# Tenk.net
KiCad netlist of a schematic drawn in Altium Designer
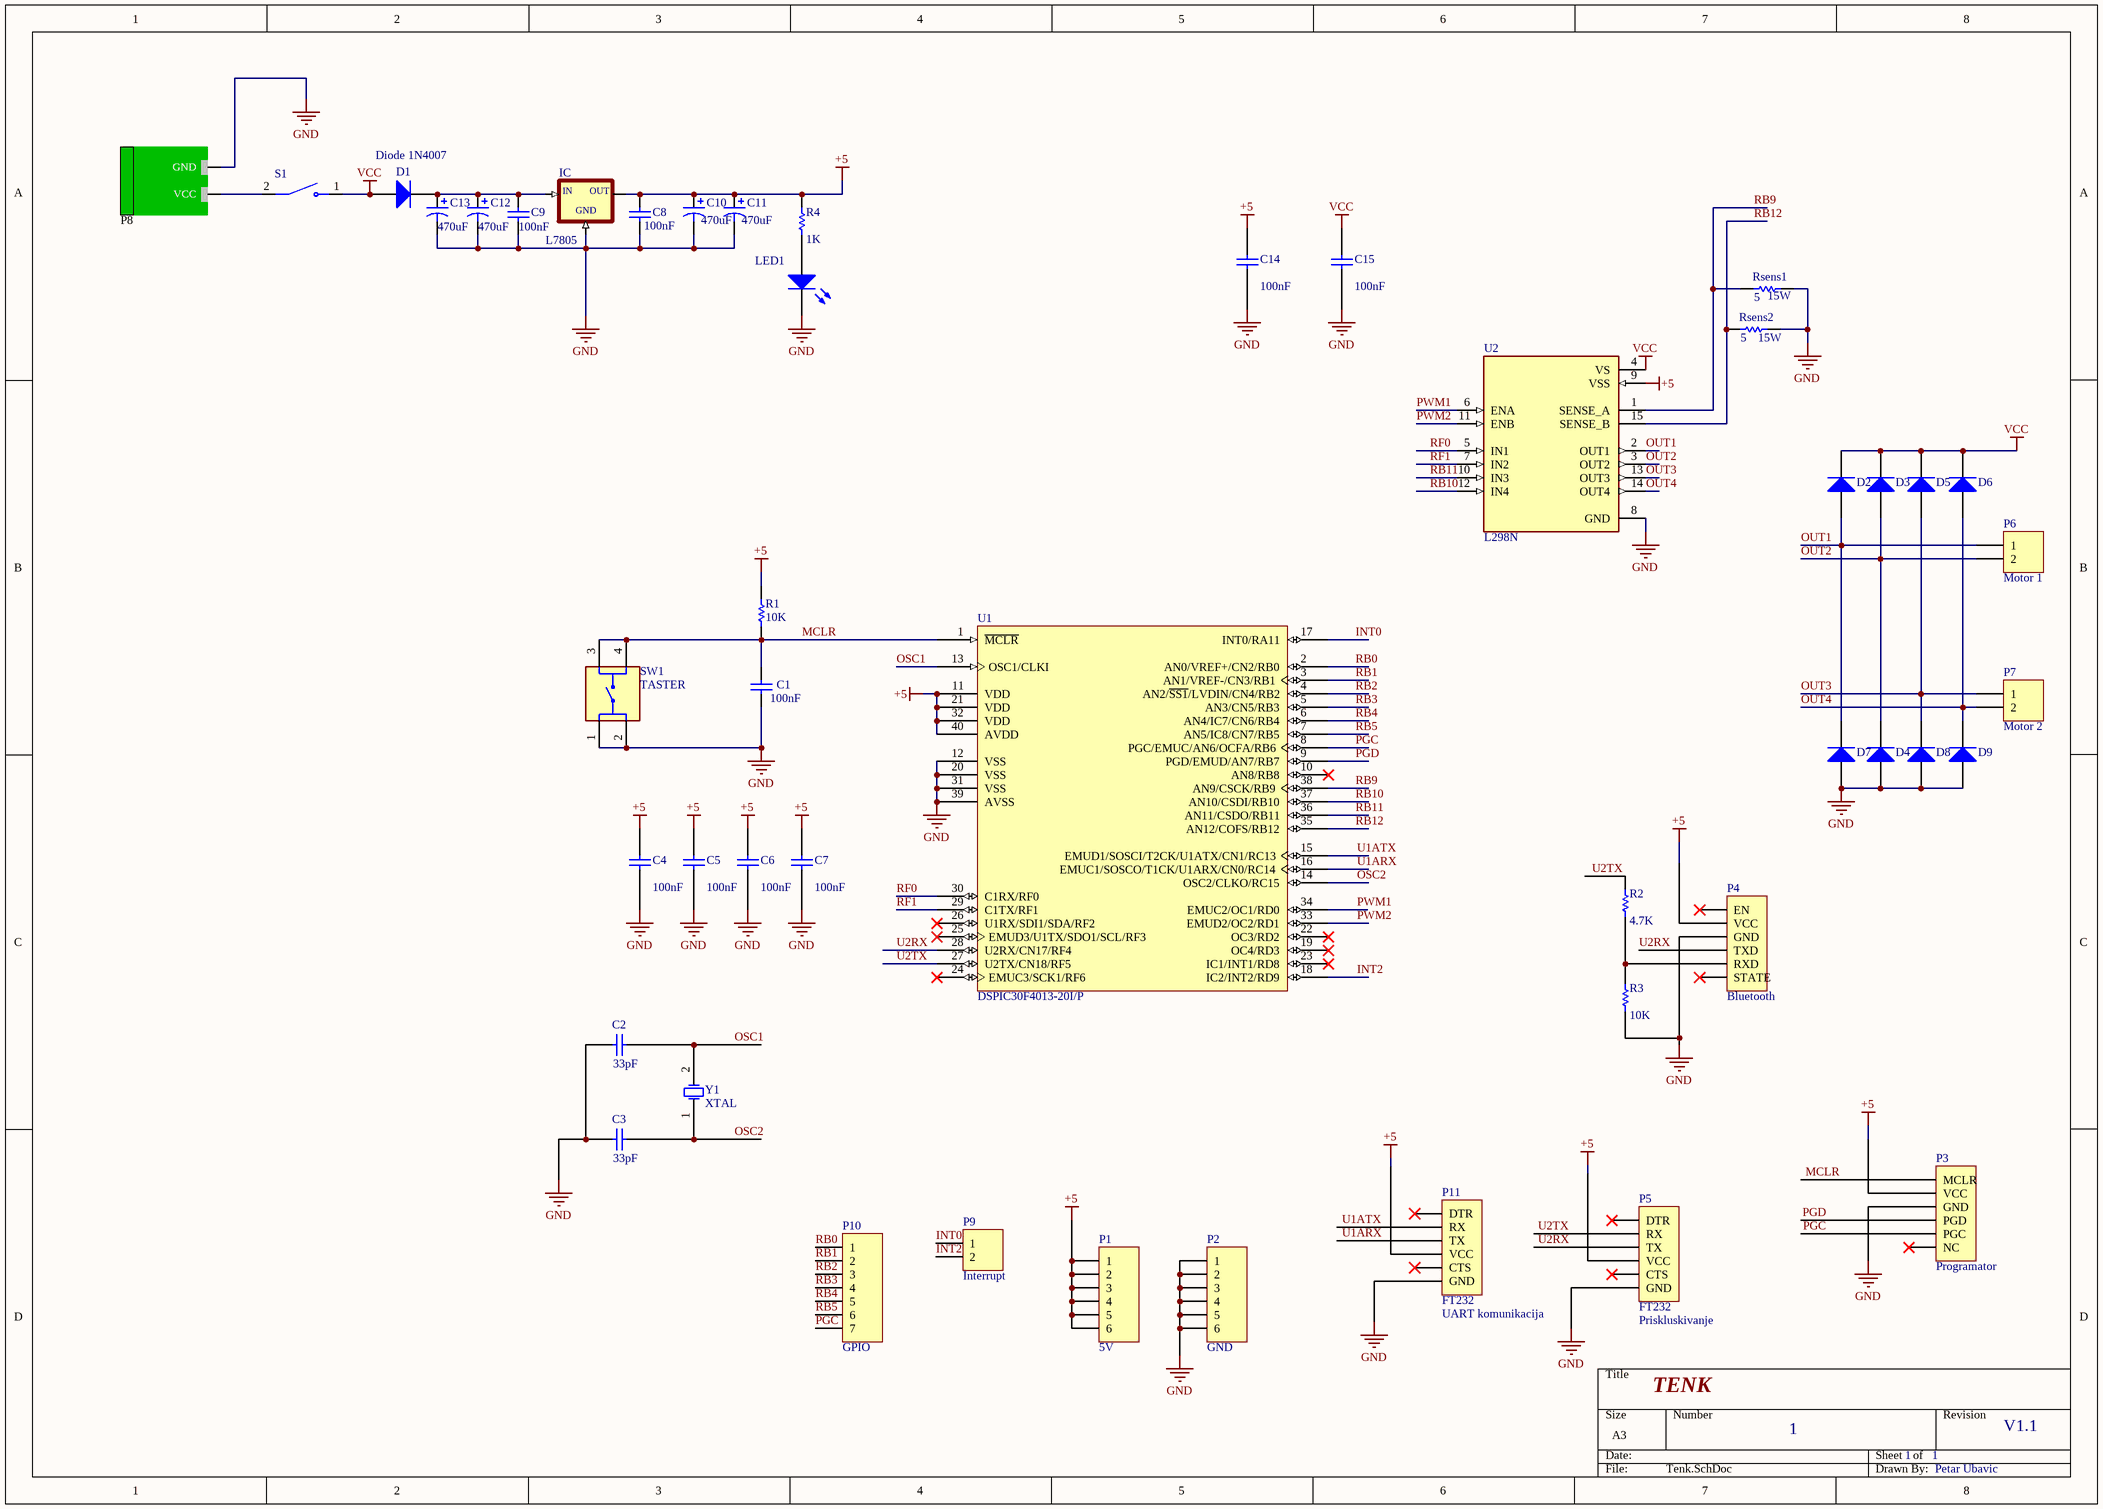
[diagram p0: Tenk.SchDoc]

(export (version "E")
  (design (tool "Eeschema 10.0.6"))
  (components
    (comp (ref "C1")
      (value "100nF")
      (footprint "CAP100")
      (description "Capacitor")
      (fields (field (name "Comment") "Cap") (field (name "PUBLISHER") "Altium Limited"))
      (libsource (lib "Miscellaneous Devices") (part "Cap"))
    )
    (comp (ref "C2")
      (value "33pF")
      (footprint "CAP100")
      (description "Capacitor")
      (fields (field (name "Comment") "Cap") (field (name "PUBLISHER") "Altium Limited"))
      (libsource (lib "Miscellaneous Devices") (part "Cap"))
    )
    (comp (ref "C3")
      (value "33pF")
      (footprint "CAP100")
      (description "Capacitor")
      (fields (field (name "Comment") "Cap") (field (name "PUBLISHER") "Altium Limited"))
      (libsource (lib "Miscellaneous Devices") (part "Cap"))
    )
    (comp (ref "C4")
      (value "100nF")
      (footprint "CAP100")
      (description "Capacitor")
      (fields (field (name "Comment") "Cap") (field (name "PUBLISHER") "Altium Limited"))
      (libsource (lib "Miscellaneous Devices") (part "Cap"))
    )
    (comp (ref "C5")
      (value "100nF")
      (footprint "CAP100")
      (description "Capacitor")
      (fields (field (name "Comment") "Cap") (field (name "PUBLISHER") "Altium Limited"))
      (libsource (lib "Miscellaneous Devices") (part "Cap"))
    )
    (comp (ref "C6")
      (value "100nF")
      (footprint "CAP100")
      (description "Capacitor")
      (fields (field (name "Comment") "Cap") (field (name "PUBLISHER") "Altium Limited"))
      (libsource (lib "Miscellaneous Devices") (part "Cap"))
    )
    (comp (ref "C7")
      (value "100nF")
      (footprint "CAP100")
      (description "Capacitor")
      (fields (field (name "Comment") "Cap") (field (name "PUBLISHER") "Altium Limited"))
      (libsource (lib "Miscellaneous Devices") (part "Cap"))
    )
    (comp (ref "C8")
      (value "100nF")
      (footprint "CAP100")
      (description "Capacitor")
      (fields (field (name "Comment") "Cap") (field (name "PUBLISHER") "Altium Limited"))
      (libsource (lib "Miscellaneous Devices") (part "Cap"))
    )
    (comp (ref "C9")
      (value "100nF")
      (footprint "CAP100")
      (description "Capacitor")
      (fields (field (name "Comment") "Cap") (field (name "PUBLISHER") "Altium Limited"))
      (libsource (lib "Miscellaneous Devices") (part "Cap"))
    )
    (comp (ref "C10")
      (value "470uF")
      (footprint "RAD4")
      (description "Polarized Capacitor (Radial)")
      (fields (field (name "Comment") "Cap Pol1") (field (name "PUBLISHER") "Altium Limited"))
      (libsource (lib "Miscellaneous Devices") (part "Cap Pol1"))
    )
    (comp (ref "C11")
      (value "470uF")
      (footprint "RAD4")
      (description "Polarized Capacitor (Radial)")
      (fields (field (name "Comment") "Cap Pol1") (field (name "PUBLISHER") "Altium Limited"))
      (libsource (lib "Miscellaneous Devices") (part "Cap Pol1"))
    )
    (comp (ref "C12")
      (value "470uF")
      (footprint "RAD4")
      (description "Polarized Capacitor (Radial)")
      (fields (field (name "Comment") "Cap Pol1") (field (name "PUBLISHER") "Altium Limited"))
      (libsource (lib "Miscellaneous Devices") (part "Cap Pol1"))
    )
    (comp (ref "C13")
      (value "470uF")
      (footprint "RAD4")
      (description "Polarized Capacitor (Radial)")
      (fields (field (name "Comment") "Cap Pol1") (field (name "PUBLISHER") "Altium Limited"))
      (libsource (lib "Miscellaneous Devices") (part "Cap Pol1"))
    )
    (comp (ref "C14")
      (value "100nF")
      (footprint "CAP100")
      (description "Capacitor")
      (fields (field (name "Comment") "Cap") (field (name "PUBLISHER") "Altium Limited"))
      (libsource (lib "Miscellaneous Devices") (part "Cap"))
    )
    (comp (ref "C15")
      (value "100nF")
      (footprint "CAP100")
      (description "Capacitor")
      (fields (field (name "Comment") "Cap") (field (name "PUBLISHER") "Altium Limited"))
      (libsource (lib "Miscellaneous Devices") (part "Cap"))
    )
    (comp (ref "D1")
      (value "Diode 1N4007")
      (footprint "DIODE400")
      (description "1 Amp General Purpose Rectifier")
      (fields (field (name "PUBLISHER") "Altium Limited"))
      (libsource (lib "Miscellaneous Devices") (part "Diode 1N4007"))
    )
    (comp (ref "D2")
      (value "Diode 1N5402")
      (footprint "DIODE400")
      (description "3 Amp General Purpose Rectifier")
      (fields (field (name "PUBLISHER") "Altium Limited"))
      (libsource (lib "Miscellaneous Devices") (part "Diode 1N5402"))
    )
    (comp (ref "D3")
      (value "Diode 1N5402")
      (footprint "DIODE400")
      (description "3 Amp General Purpose Rectifier")
      (fields (field (name "PUBLISHER") "Altium Limited"))
      (libsource (lib "Miscellaneous Devices") (part "Diode 1N5402"))
    )
    (comp (ref "D4")
      (value "Diode 1N5402")
      (footprint "DIODE400")
      (description "3 Amp General Purpose Rectifier")
      (fields (field (name "PUBLISHER") "Altium Limited"))
      (libsource (lib "Miscellaneous Devices") (part "Diode 1N5402"))
    )
    (comp (ref "D5")
      (value "Diode 1N5402")
      (footprint "DIODE400")
      (description "3 Amp General Purpose Rectifier")
      (fields (field (name "PUBLISHER") "Altium Limited"))
      (libsource (lib "Miscellaneous Devices") (part "Diode 1N5402"))
    )
    (comp (ref "D6")
      (value "Diode 1N5402")
      (footprint "DIODE400")
      (description "3 Amp General Purpose Rectifier")
      (fields (field (name "PUBLISHER") "Altium Limited"))
      (libsource (lib "Miscellaneous Devices") (part "Diode 1N5402"))
    )
    (comp (ref "D7")
      (value "Diode 1N5402")
      (footprint "DIODE400")
      (description "3 Amp General Purpose Rectifier")
      (fields (field (name "PUBLISHER") "Altium Limited"))
      (libsource (lib "Miscellaneous Devices") (part "Diode 1N5402"))
    )
    (comp (ref "D8")
      (value "Diode 1N5402")
      (footprint "DIODE400")
      (description "3 Amp General Purpose Rectifier")
      (fields (field (name "PUBLISHER") "Altium Limited"))
      (libsource (lib "Miscellaneous Devices") (part "Diode 1N5402"))
    )
    (comp (ref "D9")
      (value "Diode 1N5402")
      (footprint "DIODE400")
      (description "3 Amp General Purpose Rectifier")
      (fields (field (name "PUBLISHER") "Altium Limited"))
      (libsource (lib "Miscellaneous Devices") (part "Diode 1N5402"))
    )
    (comp (ref "IC")
      (value "L7805")
      (footprint "78XXS")
      (description "Linear Voltage Regulator IC 1 Output 1.5A D2PAK")
      (fields (field (name "MF") "STMicroelectronics"))
      (libsource (lib "L7805") (part "L7805"))
    )
    (comp (ref "LED1")
      (value "GREEN")
      (footprint "LED_2")
      (description "Typical RED GaAs LED")
      (fields (field (name "PUBLISHER") "Altium Limited"))
      (libsource (lib "Miscellaneous Devices") (part "LED1"))
    )
    (comp (ref "P1")
      (value "5V")
      (footprint "HEADER_6")
      (description "Header, 6-Pin")
      (fields (field (name "PUBLISHER") "Altium Limited"))
      (libsource (lib "Miscellaneous Connectors") (part "Header 6"))
    )
    (comp (ref "P2")
      (value "GND")
      (footprint "HEADER_6")
      (description "Header, 6-Pin")
      (fields (field (name "PUBLISHER") "Altium Limited"))
      (libsource (lib "Miscellaneous Connectors") (part "Header 6"))
    )
    (comp (ref "P3")
      (value "Programator")
      (footprint "HEADER_6")
      (description "Header, 6-Pin")
      (fields (field (name "PUBLISHER") "Altium Limited"))
      (libsource (lib "Miscellaneous Connectors") (part "Header 6"))
    )
    (comp (ref "P4")
      (value "Bluetooth")
      (footprint "HEADER_6")
      (description "Header, 6-Pin")
      (fields (field (name "PUBLISHER") "Altium Limited"))
      (libsource (lib "Miscellaneous Connectors") (part "Header 6"))
    )
    (comp (ref "P5")
      (value "FT232")
      (footprint "HEADER_6")
      (description "Header, 6-Pin")
      (fields (field (name "PUBLISHER") "Altium Limited"))
      (libsource (lib "Miscellaneous Connectors") (part "Header 6"))
    )
    (comp (ref "P6")
      (value "Motor 1")
      (footprint "KLEMA")
      (description "Header, 2-Pin")
      (fields (field (name "PUBLISHER") "Altium Limited"))
      (libsource (lib "Miscellaneous Connectors") (part "Header 2"))
    )
    (comp (ref "P7")
      (value "Motor 2")
      (footprint "KLEMA")
      (description "Header, 2-Pin")
      (fields (field (name "PUBLISHER") "Altium Limited"))
      (libsource (lib "Miscellaneous Connectors") (part "Header 2"))
    )
    (comp (ref "P8")
      (value "2EDGRC-5.08-02P-14-00A(H)")
      (footprint "PWR_Con")
      (description "TERM BLOCK HDR 2POS 90DEG 5.08MM")
      (libsource (lib "Electro_Mechanical") (part "00000002"))
    )
    (comp (ref "P9")
      (value "Interrupt")
      (footprint "HDR1X2")
      (description "Header, 2-Pin")
      (fields (field (name "PUBLISHER") "Altium Limited"))
      (libsource (lib "Miscellaneous Connectors") (part "Header 2"))
    )
    (comp (ref "P10")
      (value "GPIO")
      (footprint "HDR1X7")
      (description "Header, 7-Pin")
      (fields (field (name "PUBLISHER") "Altium Limited"))
      (libsource (lib "Miscellaneous Connectors") (part "Header 7"))
    )
    (comp (ref "P11")
      (value "FT232")
      (footprint "HEADER_6")
      (description "Header, 6-Pin")
      (fields (field (name "PUBLISHER") "Altium Limited"))
      (libsource (lib "Miscellaneous Connectors") (part "Header 6"))
    )
    (comp (ref "R1")
      (value "10K")
      (footprint "RES400")
      (description "Resistor")
      (fields (field (name "Comment") "Res1") (field (name "PUBLISHER") "Altium Limited"))
      (libsource (lib "Miscellaneous Devices") (part "Res1"))
    )
    (comp (ref "R2")
      (value "4.7K")
      (footprint "RES400")
      (description "Resistor")
      (fields (field (name "Comment") "Res1") (field (name "PUBLISHER") "Altium Limited"))
      (libsource (lib "Miscellaneous Devices") (part "Res1"))
    )
    (comp (ref "R3")
      (value "10K")
      (footprint "RES400")
      (description "Resistor")
      (fields (field (name "Comment") "Res1") (field (name "PUBLISHER") "Altium Limited"))
      (libsource (lib "Miscellaneous Devices") (part "Res1"))
    )
    (comp (ref "R4")
      (value "1K")
      (footprint "RES400")
      (description "Resistor")
      (fields (field (name "Comment") "Res1") (field (name "PUBLISHER") "Altium Limited"))
      (libsource (lib "Miscellaneous Devices") (part "Res1"))
    )
    (comp (ref "Rsens1")
      (value "15W")
      (footprint "Rsens")
      (description "Resistor")
      (fields (field (name "ALTIUM_VALUE") "5") (field (name "PUBLISHER") "Altium Limited"))
      (libsource (lib "Miscellaneous Devices") (part "Res1"))
    )
    (comp (ref "Rsens2")
      (value "15W")
      (footprint "Rsens")
      (description "Resistor")
      (fields (field (name "ALTIUM_VALUE") "5") (field (name "PUBLISHER") "Altium Limited"))
      (libsource (lib "Miscellaneous Devices") (part "Res1"))
    )
    (comp (ref "S1")
      (value "~")
      (footprint "SW_RB141C1100")
      (description "Rocker Switches 15A 125VAC, OFF-ON, Black Rocker, No Markings")
      (fields (field (name "MP") "RB141C1100") (field (name "MF") "e-switch inc"))
      (libsource (lib "RB141C1100") (part "RB141C1100"))
    )
    (comp (ref "SW1")
      (value "TASTER")
      (footprint "SW_1825910-6-4")
      (description "Switch Tactile OFF (ON) SPST Round Button PC Pins 0.05A 24VDC 100000Cycles 1.57N Thru-Hole Loose")
      (fields (field (name "MP") "1825910-6"))
      (libsource (lib "1825910-6") (part "1825910-6"))
    )
    (comp (ref "U1")
      (value "DSPIC30F4013-20I/P")
      (footprint "PDIP600-P40")
      (fields (field (name "PUBLISHER") "Altium Limited"))
      (libsource (lib "Microchip DSC 16-Bit dsPIC30F") (part "DSPIC30F4013-20I/P"))
    )
    (comp (ref "U2")
      (value "L298N")
      (footprint "TO127P2020X500X2100-15")
      (description "Dual Full Bridge Motor Driver 15-Pin(15+Tab) MULTIWATT V Tube")
      (libsource (lib "L298N") (part "L298N"))
    )
    (comp (ref "Y1")
      (value "XTAL")
      (footprint "OSC_5")
      (description "Crystal Oscillator")
      (fields (field (name "PUBLISHER") "Altium Limited"))
      (libsource (lib "Miscellaneous Devices") (part "XTAL"))
    )
  )
  (nets
    (net (code "1") (name "+5") (class "Default")
      (node (ref "C10") (pin "1") (pinfunction "1_1") (pintype "passive"))
      (node (ref "C11") (pin "1") (pinfunction "1_1") (pintype "passive"))
      (node (ref "C14") (pin "2") (pinfunction "2_2") (pintype "passive"))
      (node (ref "C4") (pin "2") (pinfunction "2_2") (pintype "passive"))
      (node (ref "C5") (pin "2") (pinfunction "2_2") (pintype "passive"))
      (node (ref "C6") (pin "2") (pinfunction "2_2") (pintype "passive"))
      (node (ref "C7") (pin "2") (pinfunction "2_2") (pintype "passive"))
      (node (ref "C8") (pin "2") (pinfunction "2_2") (pintype "passive"))
      (node (ref "IC") (pin "OUT") (pinfunction "OUT_OUT") (pintype "passive"))
      (node (ref "P1") (pin "1") (pinfunction "1_1") (pintype "passive"))
      (node (ref "P1") (pin "2") (pinfunction "2_2") (pintype "passive"))
      (node (ref "P1") (pin "3") (pinfunction "3_3") (pintype "passive"))
      (node (ref "P1") (pin "4") (pinfunction "4_4") (pintype "passive"))
      (node (ref "P1") (pin "5") (pinfunction "5_5") (pintype "passive"))
      (node (ref "P1") (pin "6") (pinfunction "6_6") (pintype "passive"))
      (node (ref "P11") (pin "4") (pinfunction "4_4") (pintype "passive"))
      (node (ref "P3") (pin "2") (pinfunction "2_2") (pintype "passive"))
      (node (ref "P4") (pin "2") (pinfunction "2_2") (pintype "passive"))
      (node (ref "P5") (pin "4") (pinfunction "4_4") (pintype "passive"))
      (node (ref "R1") (pin "2") (pinfunction "2_2") (pintype "passive"))
      (node (ref "R4") (pin "2") (pinfunction "2_2") (pintype "passive"))
      (node (ref "U1") (pin "11") (pinfunction "VDD_11") (pintype "power_in"))
      (node (ref "U1") (pin "21") (pinfunction "VDD_21") (pintype "power_in"))
      (node (ref "U1") (pin "32") (pinfunction "VDD_32") (pintype "power_in"))
      (node (ref "U1") (pin "40") (pinfunction "AVDD_40") (pintype "power_in"))
      (node (ref "U2") (pin "9") (pinfunction "VSS_9") (pintype "input"))
    )
    (net (code "2") (name "/INT0") (class "Default")
      (node (ref "P9") (pin "1") (pinfunction "1_1") (pintype "passive"))
      (node (ref "U1") (pin "17") (pinfunction "INT0/RA11_17") (pintype "bidirectional"))
    )
    (net (code "3") (name "/INT2") (class "Default")
      (node (ref "P9") (pin "2") (pinfunction "2_2") (pintype "passive"))
      (node (ref "U1") (pin "18") (pinfunction "IC2/INT2/RD9_18") (pintype "bidirectional"))
    )
    (net (code "4") (name "/MCLR") (class "Default")
      (node (ref "C1") (pin "2") (pinfunction "2_2") (pintype "passive"))
      (node (ref "P3") (pin "1") (pinfunction "1_1") (pintype "passive"))
      (node (ref "R1") (pin "1") (pinfunction "1_1") (pintype "passive"))
      (node (ref "SW1") (pin "3") (pinfunction "3_3") (pintype "passive"))
      (node (ref "SW1") (pin "4") (pinfunction "4_4") (pintype "passive"))
      (node (ref "U1") (pin "1") (pinfunction "~{MCLR}_1") (pintype "input"))
    )
    (net (code "5") (name "/OSC1") (class "Default")
      (node (ref "C2") (pin "2") (pinfunction "2_2") (pintype "passive"))
      (node (ref "U1") (pin "13") (pinfunction "OSC1/CLKI_13") (pintype "input"))
      (node (ref "Y1") (pin "2") (pinfunction "OSC2_2") (pintype "passive"))
    )
    (net (code "6") (name "/OSC2") (class "Default")
      (node (ref "C3") (pin "2") (pinfunction "2_2") (pintype "passive"))
      (node (ref "U1") (pin "14") (pinfunction "OSC2/CLKO/RC15_14") (pintype "bidirectional"))
      (node (ref "Y1") (pin "1") (pinfunction "OSC1_1") (pintype "passive"))
    )
    (net (code "7") (name "/OUT1") (class "Default")
      (node (ref "D2") (pin "1") (pinfunction "A_1") (pintype "passive"))
      (node (ref "D7") (pin "2") (pinfunction "K_2") (pintype "passive"))
      (node (ref "P6") (pin "1") (pinfunction "1_1") (pintype "passive"))
      (node (ref "U2") (pin "2") (pinfunction "OUT1_2") (pintype "output"))
    )
    (net (code "8") (name "/OUT2") (class "Default")
      (node (ref "D3") (pin "1") (pinfunction "A_1") (pintype "passive"))
      (node (ref "D4") (pin "2") (pinfunction "K_2") (pintype "passive"))
      (node (ref "P6") (pin "2") (pinfunction "2_2") (pintype "passive"))
      (node (ref "U2") (pin "3") (pinfunction "OUT2_3") (pintype "output"))
    )
    (net (code "9") (name "/OUT3") (class "Default")
      (node (ref "D5") (pin "1") (pinfunction "A_1") (pintype "passive"))
      (node (ref "D8") (pin "2") (pinfunction "K_2") (pintype "passive"))
      (node (ref "P7") (pin "1") (pinfunction "1_1") (pintype "passive"))
      (node (ref "U2") (pin "13") (pinfunction "OUT3_13") (pintype "output"))
    )
    (net (code "10") (name "/OUT4") (class "Default")
      (node (ref "D6") (pin "1") (pinfunction "A_1") (pintype "passive"))
      (node (ref "D9") (pin "2") (pinfunction "K_2") (pintype "passive"))
      (node (ref "P7") (pin "2") (pinfunction "2_2") (pintype "passive"))
      (node (ref "U2") (pin "14") (pinfunction "OUT4_14") (pintype "output"))
    )
    (net (code "11") (name "/PGC") (class "Default")
      (node (ref "P10") (pin "7") (pinfunction "7_7") (pintype "passive"))
      (node (ref "P3") (pin "5") (pinfunction "5_5") (pintype "passive"))
      (node (ref "U1") (pin "8") (pinfunction "PGC/EMUC/AN6/OCFA/RB6_8") (pintype "bidirectional"))
    )
    (net (code "12") (name "/PGD") (class "Default")
      (node (ref "P3") (pin "4") (pinfunction "4_4") (pintype "passive"))
      (node (ref "U1") (pin "9") (pinfunction "PGD/EMUD/AN7/RB7_9") (pintype "bidirectional"))
    )
    (net (code "13") (name "/PWM1") (class "Default")
      (node (ref "U1") (pin "34") (pinfunction "EMUC2/OC1/RD0_34") (pintype "bidirectional"))
      (node (ref "U2") (pin "6") (pinfunction "ENA_6") (pintype "input"))
    )
    (net (code "14") (name "/PWM2") (class "Default")
      (node (ref "U1") (pin "33") (pinfunction "EMUD2/OC2/RD1_33") (pintype "bidirectional"))
      (node (ref "U2") (pin "11") (pinfunction "ENB_11") (pintype "input"))
    )
    (net (code "15") (name "/RB0") (class "Default")
      (node (ref "P10") (pin "1") (pinfunction "1_1") (pintype "passive"))
      (node (ref "U1") (pin "2") (pinfunction "AN0/VREF+/CN2/RB0_2") (pintype "bidirectional"))
    )
    (net (code "16") (name "/RB1") (class "Default")
      (node (ref "P10") (pin "2") (pinfunction "2_2") (pintype "passive"))
      (node (ref "U1") (pin "3") (pinfunction "AN1/VREF-/CN3/RB1_3") (pintype "bidirectional"))
    )
    (net (code "17") (name "/RB2") (class "Default")
      (node (ref "P10") (pin "3") (pinfunction "3_3") (pintype "passive"))
      (node (ref "U1") (pin "4") (pinfunction "AN2/~{SS1}/LVDIN/CN4/RB2_4") (pintype "bidirectional"))
    )
    (net (code "18") (name "/RB3") (class "Default")
      (node (ref "P10") (pin "4") (pinfunction "4_4") (pintype "passive"))
      (node (ref "U1") (pin "5") (pinfunction "AN3/CN5/RB3_5") (pintype "bidirectional"))
    )
    (net (code "19") (name "/RB4") (class "Default")
      (node (ref "P10") (pin "5") (pinfunction "5_5") (pintype "passive"))
      (node (ref "U1") (pin "6") (pinfunction "AN4/IC7/CN6/RB4_6") (pintype "bidirectional"))
    )
    (net (code "20") (name "/RB5") (class "Default")
      (node (ref "P10") (pin "6") (pinfunction "6_6") (pintype "passive"))
      (node (ref "U1") (pin "7") (pinfunction "AN5/IC8/CN7/RB5_7") (pintype "bidirectional"))
    )
    (net (code "21") (name "/RB9") (class "Default")
      (node (ref "Rsens1") (pin "1") (pinfunction "1_1") (pintype "passive"))
      (node (ref "U1") (pin "38") (pinfunction "AN9/CSCK/RB9_38") (pintype "bidirectional"))
      (node (ref "U2") (pin "1") (pinfunction "SENSE_A_1") (pintype "passive"))
    )
    (net (code "22") (name "/RB10") (class "Default")
      (node (ref "U1") (pin "37") (pinfunction "AN10/CSDI/RB10_37") (pintype "bidirectional"))
      (node (ref "U2") (pin "12") (pinfunction "IN4_12") (pintype "input"))
    )
    (net (code "23") (name "/RB11") (class "Default")
      (node (ref "U1") (pin "36") (pinfunction "AN11/CSDO/RB11_36") (pintype "bidirectional"))
      (node (ref "U2") (pin "10") (pinfunction "IN3_10") (pintype "input"))
    )
    (net (code "24") (name "/RB12") (class "Default")
      (node (ref "Rsens2") (pin "1") (pinfunction "1_1") (pintype "passive"))
      (node (ref "U1") (pin "35") (pinfunction "AN12/COFS/RB12_35") (pintype "bidirectional"))
      (node (ref "U2") (pin "15") (pinfunction "SENSE_B_15") (pintype "passive"))
    )
    (net (code "25") (name "/RF0") (class "Default")
      (node (ref "U1") (pin "30") (pinfunction "C1RX/RF0_30") (pintype "bidirectional"))
      (node (ref "U2") (pin "5") (pinfunction "IN1_5") (pintype "input"))
    )
    (net (code "26") (name "/RF1") (class "Default")
      (node (ref "U1") (pin "29") (pinfunction "C1TX/RF1_29") (pintype "bidirectional"))
      (node (ref "U2") (pin "7") (pinfunction "IN2_7") (pintype "input"))
    )
    (net (code "27") (name "/U1ARX") (class "Default")
      (node (ref "P11") (pin "3") (pinfunction "3_3") (pintype "passive"))
      (node (ref "U1") (pin "16") (pinfunction "EMUC1/SOSCO/T1CK/U1ARX/CN0/RC14_16") (pintype "bidirectional"))
    )
    (net (code "28") (name "/U1ATX") (class "Default")
      (node (ref "P11") (pin "2") (pinfunction "2_2") (pintype "passive"))
      (node (ref "U1") (pin "15") (pinfunction "EMUD1/SOSCI/T2CK/U1ATX/CN1/RC13_15") (pintype "bidirectional"))
    )
    (net (code "29") (name "/U2RX") (class "Default")
      (node (ref "P4") (pin "4") (pinfunction "4_4") (pintype "passive"))
      (node (ref "P5") (pin "3") (pinfunction "3_3") (pintype "passive"))
      (node (ref "U1") (pin "28") (pinfunction "U2RX/CN17/RF4_28") (pintype "bidirectional"))
    )
    (net (code "30") (name "/U2TX") (class "Default")
      (node (ref "P5") (pin "2") (pinfunction "2_2") (pintype "passive"))
      (node (ref "R2") (pin "2") (pinfunction "2_2") (pintype "passive"))
      (node (ref "U1") (pin "27") (pinfunction "U2TX/CN18/RF5_27") (pintype "bidirectional"))
    )
    (net (code "31") (name "GND") (class "Default")
      (node (ref "C1") (pin "1") (pinfunction "1_1") (pintype "passive"))
      (node (ref "C10") (pin "2") (pinfunction "2_2") (pintype "passive"))
      (node (ref "C11") (pin "2") (pinfunction "2_2") (pintype "passive"))
      (node (ref "C12") (pin "2") (pinfunction "2_2") (pintype "passive"))
      (node (ref "C13") (pin "2") (pinfunction "2_2") (pintype "passive"))
      (node (ref "C14") (pin "1") (pinfunction "1_1") (pintype "passive"))
      (node (ref "C15") (pin "1") (pinfunction "1_1") (pintype "passive"))
      (node (ref "C2") (pin "1") (pinfunction "1_1") (pintype "passive"))
      (node (ref "C3") (pin "1") (pinfunction "1_1") (pintype "passive"))
      (node (ref "C4") (pin "1") (pinfunction "1_1") (pintype "passive"))
      (node (ref "C5") (pin "1") (pinfunction "1_1") (pintype "passive"))
      (node (ref "C6") (pin "1") (pinfunction "1_1") (pintype "passive"))
      (node (ref "C7") (pin "1") (pinfunction "1_1") (pintype "passive"))
      (node (ref "C8") (pin "1") (pinfunction "1_1") (pintype "passive"))
      (node (ref "C9") (pin "1") (pinfunction "1_1") (pintype "passive"))
      (node (ref "D4") (pin "1") (pinfunction "A_1") (pintype "passive"))
      (node (ref "D7") (pin "1") (pinfunction "A_1") (pintype "passive"))
      (node (ref "D8") (pin "1") (pinfunction "A_1") (pintype "passive"))
      (node (ref "D9") (pin "1") (pinfunction "A_1") (pintype "passive"))
      (node (ref "IC") (pin "GND") (pinfunction "GND_GND") (pintype "input"))
      (node (ref "LED1") (pin "2") (pinfunction "K_2") (pintype "passive"))
      (node (ref "P11") (pin "6") (pinfunction "6_6") (pintype "passive"))
      (node (ref "P2") (pin "1") (pinfunction "1_1") (pintype "passive"))
      (node (ref "P2") (pin "2") (pinfunction "2_2") (pintype "passive"))
      (node (ref "P2") (pin "3") (pinfunction "3_3") (pintype "passive"))
      (node (ref "P2") (pin "4") (pinfunction "4_4") (pintype "passive"))
      (node (ref "P2") (pin "5") (pinfunction "5_5") (pintype "passive"))
      (node (ref "P2") (pin "6") (pinfunction "6_6") (pintype "passive"))
      (node (ref "P3") (pin "3") (pinfunction "3_3") (pintype "passive"))
      (node (ref "P4") (pin "3") (pinfunction "3_3") (pintype "passive"))
      (node (ref "P5") (pin "6") (pinfunction "6_6") (pintype "passive"))
      (node (ref "P8") (pin "1") (pinfunction "GND_1") (pintype "passive"))
      (node (ref "R3") (pin "1") (pinfunction "1_1") (pintype "passive"))
      (node (ref "Rsens1") (pin "2") (pinfunction "2_2") (pintype "passive"))
      (node (ref "Rsens2") (pin "2") (pinfunction "2_2") (pintype "passive"))
      (node (ref "SW1") (pin "1") (pinfunction "1_1") (pintype "passive"))
      (node (ref "SW1") (pin "2") (pinfunction "2_2") (pintype "passive"))
      (node (ref "U1") (pin "12") (pinfunction "VSS_12") (pintype "power_in"))
      (node (ref "U1") (pin "20") (pinfunction "VSS_20") (pintype "power_in"))
      (node (ref "U1") (pin "31") (pinfunction "VSS_31") (pintype "power_in"))
      (node (ref "U1") (pin "39") (pinfunction "AVSS_39") (pintype "power_in"))
      (node (ref "U2") (pin "8") (pinfunction "GND_8") (pintype "power_in"))
    )
    (net (code "32") (name "Net-(D1-K)") (class "Default")
      (node (ref "C12") (pin "1") (pinfunction "1_1") (pintype "passive"))
      (node (ref "C13") (pin "1") (pinfunction "1_1") (pintype "passive"))
      (node (ref "C9") (pin "2") (pinfunction "2_2") (pintype "passive"))
      (node (ref "D1") (pin "2") (pinfunction "K_2") (pintype "passive"))
      (node (ref "IC") (pin "IN") (pinfunction "IN_IN") (pintype "input"))
    )
    (net (code "33") (name "Net-(LED1-A)") (class "Default")
      (node (ref "LED1") (pin "1") (pinfunction "A_1") (pintype "passive"))
      (node (ref "R4") (pin "1") (pinfunction "1_1") (pintype "passive"))
    )
    (net (code "34") (name "Net-(P4-Pad5)") (class "Default")
      (node (ref "P4") (pin "5") (pinfunction "5_5") (pintype "passive"))
      (node (ref "R2") (pin "1") (pinfunction "1_1") (pintype "passive"))
      (node (ref "R3") (pin "2") (pinfunction "2_2") (pintype "passive"))
    )
    (net (code "35") (name "Net-(P8-VCC)") (class "Default")
      (node (ref "P8") (pin "2") (pinfunction "VCC_2") (pintype "passive"))
      (node (ref "S1") (pin "2") (pinfunction "2_2") (pintype "passive"))
    )
    (net (code "36") (name "VCC") (class "Default")
      (node (ref "C15") (pin "2") (pinfunction "2_2") (pintype "passive"))
      (node (ref "D1") (pin "1") (pinfunction "A_1") (pintype "passive"))
      (node (ref "D2") (pin "2") (pinfunction "K_2") (pintype "passive"))
      (node (ref "D3") (pin "2") (pinfunction "K_2") (pintype "passive"))
      (node (ref "D5") (pin "2") (pinfunction "K_2") (pintype "passive"))
      (node (ref "D6") (pin "2") (pinfunction "K_2") (pintype "passive"))
      (node (ref "S1") (pin "1") (pinfunction "1_1") (pintype "passive"))
      (node (ref "U2") (pin "4") (pinfunction "VS_4") (pintype "power_in"))
    )
    (net (code "37") (name "unconnected-(P3-Pad6)") (class "Default")
      (node (ref "P3") (pin "6") (pinfunction "6_6") (pintype "passive+no_connect"))
    )
    (net (code "38") (name "unconnected-(P4-Pad1)") (class "Default")
      (node (ref "P4") (pin "1") (pinfunction "1_1") (pintype "passive+no_connect"))
    )
    (net (code "39") (name "unconnected-(P4-Pad6)") (class "Default")
      (node (ref "P4") (pin "6") (pinfunction "6_6") (pintype "passive+no_connect"))
    )
    (net (code "40") (name "unconnected-(P5-Pad1)") (class "Default")
      (node (ref "P5") (pin "1") (pinfunction "1_1") (pintype "passive+no_connect"))
    )
    (net (code "41") (name "unconnected-(P5-Pad5)") (class "Default")
      (node (ref "P5") (pin "5") (pinfunction "5_5") (pintype "passive+no_connect"))
    )
    (net (code "42") (name "unconnected-(P11-Pad1)") (class "Default")
      (node (ref "P11") (pin "1") (pinfunction "1_1") (pintype "passive+no_connect"))
    )
    (net (code "43") (name "unconnected-(P11-Pad5)") (class "Default")
      (node (ref "P11") (pin "5") (pinfunction "5_5") (pintype "passive+no_connect"))
    )
    (net (code "44") (name "unconnected-(U1-AN8{slash}RB8-Pad10)") (class "Default")
      (node (ref "U1") (pin "10") (pinfunction "AN8/RB8_10") (pintype "bidirectional+no_connect"))
    )
    (net (code "45") (name "unconnected-(U1-EMUC3{slash}SCK1{slash}RF6-Pad24)") (class "Default")
      (node (ref "U1") (pin "24") (pinfunction "EMUC3/SCK1/RF6_24") (pintype "bidirectional+no_connect"))
    )
    (net (code "46") (name "unconnected-(U1-EMUD3{slash}U1TX{slash}SDO1{slash}SCL{slash}RF3-Pad25)") (class "Default")
      (node (ref "U1") (pin "25") (pinfunction "EMUD3/U1TX/SDO1/SCL/RF3_25") (pintype "bidirectional+no_connect"))
    )
    (net (code "47") (name "unconnected-(U1-IC1{slash}INT1{slash}RD8-Pad23)") (class "Default")
      (node (ref "U1") (pin "23") (pinfunction "IC1/INT1/RD8_23") (pintype "bidirectional+no_connect"))
    )
    (net (code "48") (name "unconnected-(U1-OC3{slash}RD2-Pad22)") (class "Default")
      (node (ref "U1") (pin "22") (pinfunction "OC3/RD2_22") (pintype "bidirectional+no_connect"))
    )
    (net (code "49") (name "unconnected-(U1-OC4{slash}RD3-Pad19)") (class "Default")
      (node (ref "U1") (pin "19") (pinfunction "OC4/RD3_19") (pintype "bidirectional+no_connect"))
    )
    (net (code "50") (name "unconnected-(U1-U1RX{slash}SDI1{slash}SDA{slash}RF2-Pad26)") (class "Default")
      (node (ref "U1") (pin "26") (pinfunction "U1RX/SDI1/SDA/RF2_26") (pintype "bidirectional+no_connect"))
    )
  )
)
